# NeoPixel-WS2812B-2020.net
KiCad netlist of a schematic drawn in EAGLE
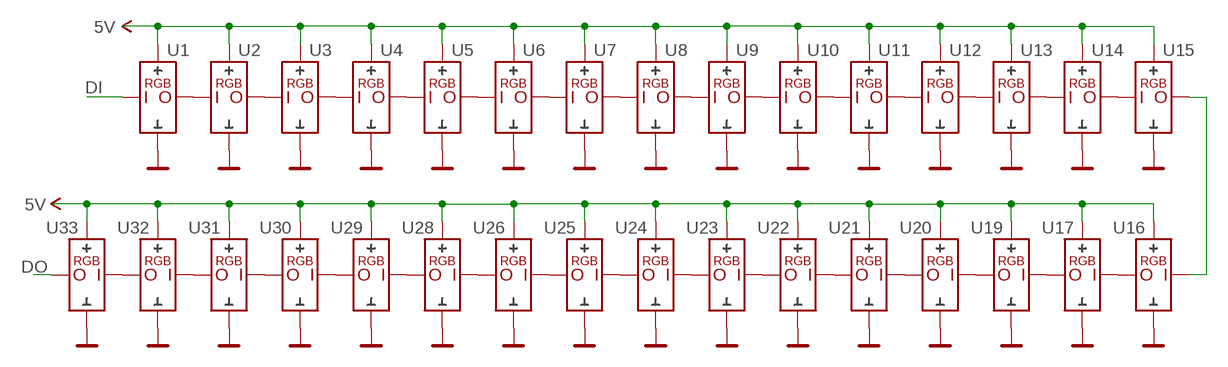
[diagram p0: schematic, sheet 1]

(export (version "E")
  (design (tool "Eeschema 10.0.6"))
  (components
    (comp (ref "U1")
      (value "LED-ADDRESSABLE16MM")
      (footprint "eagle-import:LED-WS2812B-2020-RING")
      (libsource (lib "eagle-import") (part "LED-ADDRESSABLE16MM"))
    )
    (comp (ref "U2")
      (value "LED-ADDRESSABLE16MM")
      (footprint "eagle-import:LED-WS2812B-2020-RING")
      (libsource (lib "eagle-import") (part "LED-ADDRESSABLE16MM"))
    )
    (comp (ref "U3")
      (value "LED-ADDRESSABLE16MM")
      (footprint "eagle-import:LED-WS2812B-2020-RING")
      (libsource (lib "eagle-import") (part "LED-ADDRESSABLE16MM"))
    )
    (comp (ref "U4")
      (value "LED-ADDRESSABLE16MM")
      (footprint "eagle-import:LED-WS2812B-2020-RING")
      (libsource (lib "eagle-import") (part "LED-ADDRESSABLE16MM"))
    )
    (comp (ref "U5")
      (value "LED-ADDRESSABLE16MM")
      (footprint "eagle-import:LED-WS2812B-2020-RING")
      (libsource (lib "eagle-import") (part "LED-ADDRESSABLE16MM"))
    )
    (comp (ref "U6")
      (value "LED-ADDRESSABLE16MM")
      (footprint "eagle-import:LED-WS2812B-2020-RING")
      (libsource (lib "eagle-import") (part "LED-ADDRESSABLE16MM"))
    )
    (comp (ref "U7")
      (value "LED-ADDRESSABLE16MM")
      (footprint "eagle-import:LED-WS2812B-2020-RING")
      (libsource (lib "eagle-import") (part "LED-ADDRESSABLE16MM"))
    )
    (comp (ref "U8")
      (value "LED-ADDRESSABLE16MM")
      (footprint "eagle-import:LED-WS2812B-2020-RING")
      (libsource (lib "eagle-import") (part "LED-ADDRESSABLE16MM"))
    )
    (comp (ref "U9")
      (value "LED-ADDRESSABLE16MM")
      (footprint "eagle-import:LED-WS2812B-2020-RING")
      (libsource (lib "eagle-import") (part "LED-ADDRESSABLE16MM"))
    )
    (comp (ref "U10")
      (value "LED-ADDRESSABLE16MM")
      (footprint "eagle-import:LED-WS2812B-2020-RING")
      (libsource (lib "eagle-import") (part "LED-ADDRESSABLE16MM"))
    )
    (comp (ref "U11")
      (value "LED-ADDRESSABLE16MM")
      (footprint "eagle-import:LED-WS2812B-2020-RING")
      (libsource (lib "eagle-import") (part "LED-ADDRESSABLE16MM"))
    )
    (comp (ref "U12")
      (value "LED-ADDRESSABLE16MM")
      (footprint "eagle-import:LED-WS2812B-2020-RING")
      (libsource (lib "eagle-import") (part "LED-ADDRESSABLE16MM"))
    )
    (comp (ref "U13")
      (value "LED-ADDRESSABLE16MM")
      (footprint "eagle-import:LED-WS2812B-2020-RING")
      (libsource (lib "eagle-import") (part "LED-ADDRESSABLE16MM"))
    )
    (comp (ref "U14")
      (value "LED-ADDRESSABLE16MM")
      (footprint "eagle-import:LED-WS2812B-2020-RING")
      (libsource (lib "eagle-import") (part "LED-ADDRESSABLE16MM"))
    )
    (comp (ref "U15")
      (value "LED-ADDRESSABLE16MM")
      (footprint "eagle-import:LED-WS2812B-2020-RING")
      (libsource (lib "eagle-import") (part "LED-ADDRESSABLE16MM"))
    )
    (comp (ref "U16")
      (value "LED-ADDRESSABLE16MM")
      (footprint "eagle-import:LED-WS2812B-2020-RING")
      (libsource (lib "eagle-import") (part "LED-ADDRESSABLE16MM"))
    )
    (comp (ref "U17")
      (value "LED-ADDRESSABLE16MM")
      (footprint "eagle-import:LED-WS2812B-2020-RING")
      (libsource (lib "eagle-import") (part "LED-ADDRESSABLE16MM"))
    )
    (comp (ref "U19")
      (value "LED-ADDRESSABLE16MM")
      (footprint "eagle-import:LED-WS2812B-2020-RING")
      (libsource (lib "eagle-import") (part "LED-ADDRESSABLE16MM"))
    )
    (comp (ref "U20")
      (value "LED-ADDRESSABLE16MM")
      (footprint "eagle-import:LED-WS2812B-2020-RING")
      (libsource (lib "eagle-import") (part "LED-ADDRESSABLE16MM"))
    )
    (comp (ref "U21")
      (value "LED-ADDRESSABLE16MM")
      (footprint "eagle-import:LED-WS2812B-2020-RING")
      (libsource (lib "eagle-import") (part "LED-ADDRESSABLE16MM"))
    )
    (comp (ref "U22")
      (value "LED-ADDRESSABLE16MM")
      (footprint "eagle-import:LED-WS2812B-2020-RING")
      (libsource (lib "eagle-import") (part "LED-ADDRESSABLE16MM"))
    )
    (comp (ref "U23")
      (value "LED-ADDRESSABLE16MM")
      (footprint "eagle-import:LED-WS2812B-2020-RING")
      (libsource (lib "eagle-import") (part "LED-ADDRESSABLE16MM"))
    )
    (comp (ref "U24")
      (value "LED-ADDRESSABLE16MM")
      (footprint "eagle-import:LED-WS2812B-2020-RING")
      (libsource (lib "eagle-import") (part "LED-ADDRESSABLE16MM"))
    )
    (comp (ref "U25")
      (value "LED-ADDRESSABLE16MM")
      (footprint "eagle-import:LED-WS2812B-2020-RING")
      (libsource (lib "eagle-import") (part "LED-ADDRESSABLE16MM"))
    )
    (comp (ref "U26")
      (value "LED-ADDRESSABLE16MM")
      (footprint "eagle-import:LED-WS2812B-2020-RING")
      (libsource (lib "eagle-import") (part "LED-ADDRESSABLE16MM"))
    )
    (comp (ref "U28")
      (value "LED-ADDRESSABLE16MM")
      (footprint "eagle-import:LED-WS2812B-2020-RING")
      (libsource (lib "eagle-import") (part "LED-ADDRESSABLE16MM"))
    )
    (comp (ref "U29")
      (value "LED-ADDRESSABLE16MM")
      (footprint "eagle-import:LED-WS2812B-2020-RING")
      (libsource (lib "eagle-import") (part "LED-ADDRESSABLE16MM"))
    )
    (comp (ref "U30")
      (value "LED-ADDRESSABLE16MM")
      (footprint "eagle-import:LED-WS2812B-2020-RING")
      (libsource (lib "eagle-import") (part "LED-ADDRESSABLE16MM"))
    )
    (comp (ref "U31")
      (value "LED-ADDRESSABLE16MM")
      (footprint "eagle-import:LED-WS2812B-2020-RING")
      (libsource (lib "eagle-import") (part "LED-ADDRESSABLE16MM"))
    )
    (comp (ref "U32")
      (value "LED-ADDRESSABLE16MM")
      (footprint "eagle-import:LED-WS2812B-2020-RING")
      (libsource (lib "eagle-import") (part "LED-ADDRESSABLE16MM"))
    )
    (comp (ref "U33")
      (value "LED-ADDRESSABLE16MM")
      (footprint "eagle-import:LED-WS2812B-2020-RING")
      (libsource (lib "eagle-import") (part "LED-ADDRESSABLE16MM"))
    )
  )
  (nets
    (net (code "1") (name "/5V") (class "Default")
      (node (ref "U1") (pin "+") (pinfunction "VDD_+") (pintype "bidirectional"))
      (node (ref "U10") (pin "+") (pinfunction "VDD_+") (pintype "bidirectional"))
      (node (ref "U11") (pin "+") (pinfunction "VDD_+") (pintype "bidirectional"))
      (node (ref "U12") (pin "+") (pinfunction "VDD_+") (pintype "bidirectional"))
      (node (ref "U13") (pin "+") (pinfunction "VDD_+") (pintype "bidirectional"))
      (node (ref "U14") (pin "+") (pinfunction "VDD_+") (pintype "bidirectional"))
      (node (ref "U15") (pin "+") (pinfunction "VDD_+") (pintype "bidirectional"))
      (node (ref "U16") (pin "+") (pinfunction "VDD_+") (pintype "bidirectional"))
      (node (ref "U17") (pin "+") (pinfunction "VDD_+") (pintype "bidirectional"))
      (node (ref "U19") (pin "+") (pinfunction "VDD_+") (pintype "bidirectional"))
      (node (ref "U2") (pin "+") (pinfunction "VDD_+") (pintype "bidirectional"))
      (node (ref "U20") (pin "+") (pinfunction "VDD_+") (pintype "bidirectional"))
      (node (ref "U21") (pin "+") (pinfunction "VDD_+") (pintype "bidirectional"))
      (node (ref "U22") (pin "+") (pinfunction "VDD_+") (pintype "bidirectional"))
      (node (ref "U23") (pin "+") (pinfunction "VDD_+") (pintype "bidirectional"))
      (node (ref "U24") (pin "+") (pinfunction "VDD_+") (pintype "bidirectional"))
      (node (ref "U25") (pin "+") (pinfunction "VDD_+") (pintype "bidirectional"))
      (node (ref "U26") (pin "+") (pinfunction "VDD_+") (pintype "bidirectional"))
      (node (ref "U28") (pin "+") (pinfunction "VDD_+") (pintype "bidirectional"))
      (node (ref "U29") (pin "+") (pinfunction "VDD_+") (pintype "bidirectional"))
      (node (ref "U3") (pin "+") (pinfunction "VDD_+") (pintype "bidirectional"))
      (node (ref "U30") (pin "+") (pinfunction "VDD_+") (pintype "bidirectional"))
      (node (ref "U31") (pin "+") (pinfunction "VDD_+") (pintype "bidirectional"))
      (node (ref "U32") (pin "+") (pinfunction "VDD_+") (pintype "bidirectional"))
      (node (ref "U33") (pin "+") (pinfunction "VDD_+") (pintype "bidirectional"))
      (node (ref "U4") (pin "+") (pinfunction "VDD_+") (pintype "bidirectional"))
      (node (ref "U5") (pin "+") (pinfunction "VDD_+") (pintype "bidirectional"))
      (node (ref "U6") (pin "+") (pinfunction "VDD_+") (pintype "bidirectional"))
      (node (ref "U7") (pin "+") (pinfunction "VDD_+") (pintype "bidirectional"))
      (node (ref "U8") (pin "+") (pinfunction "VDD_+") (pintype "bidirectional"))
      (node (ref "U9") (pin "+") (pinfunction "VDD_+") (pintype "bidirectional"))
    )
    (net (code "2") (name "/DI") (class "Default")
      (node (ref "U1") (pin "DI") (pinfunction "DI_DI") (pintype "bidirectional"))
    )
    (net (code "3") (name "/DO") (class "Default")
      (node (ref "U33") (pin "DO") (pinfunction "DO_DO") (pintype "bidirectional"))
    )
    (net (code "4") (name "GND") (class "Default")
      (node (ref "U1") (pin "GND") (pinfunction "GND_GND") (pintype "bidirectional"))
      (node (ref "U10") (pin "GND") (pinfunction "GND_GND") (pintype "bidirectional"))
      (node (ref "U11") (pin "GND") (pinfunction "GND_GND") (pintype "bidirectional"))
      (node (ref "U12") (pin "GND") (pinfunction "GND_GND") (pintype "bidirectional"))
      (node (ref "U13") (pin "GND") (pinfunction "GND_GND") (pintype "bidirectional"))
      (node (ref "U14") (pin "GND") (pinfunction "GND_GND") (pintype "bidirectional"))
      (node (ref "U15") (pin "GND") (pinfunction "GND_GND") (pintype "bidirectional"))
      (node (ref "U16") (pin "GND") (pinfunction "GND_GND") (pintype "bidirectional"))
      (node (ref "U17") (pin "GND") (pinfunction "GND_GND") (pintype "bidirectional"))
      (node (ref "U19") (pin "GND") (pinfunction "GND_GND") (pintype "bidirectional"))
      (node (ref "U2") (pin "GND") (pinfunction "GND_GND") (pintype "bidirectional"))
      (node (ref "U20") (pin "GND") (pinfunction "GND_GND") (pintype "bidirectional"))
      (node (ref "U21") (pin "GND") (pinfunction "GND_GND") (pintype "bidirectional"))
      (node (ref "U22") (pin "GND") (pinfunction "GND_GND") (pintype "bidirectional"))
      (node (ref "U23") (pin "GND") (pinfunction "GND_GND") (pintype "bidirectional"))
      (node (ref "U24") (pin "GND") (pinfunction "GND_GND") (pintype "bidirectional"))
      (node (ref "U25") (pin "GND") (pinfunction "GND_GND") (pintype "bidirectional"))
      (node (ref "U26") (pin "GND") (pinfunction "GND_GND") (pintype "bidirectional"))
      (node (ref "U28") (pin "GND") (pinfunction "GND_GND") (pintype "bidirectional"))
      (node (ref "U29") (pin "GND") (pinfunction "GND_GND") (pintype "bidirectional"))
      (node (ref "U3") (pin "GND") (pinfunction "GND_GND") (pintype "bidirectional"))
      (node (ref "U30") (pin "GND") (pinfunction "GND_GND") (pintype "bidirectional"))
      (node (ref "U31") (pin "GND") (pinfunction "GND_GND") (pintype "bidirectional"))
      (node (ref "U32") (pin "GND") (pinfunction "GND_GND") (pintype "bidirectional"))
      (node (ref "U33") (pin "GND") (pinfunction "GND_GND") (pintype "bidirectional"))
      (node (ref "U4") (pin "GND") (pinfunction "GND_GND") (pintype "bidirectional"))
      (node (ref "U5") (pin "GND") (pinfunction "GND_GND") (pintype "bidirectional"))
      (node (ref "U6") (pin "GND") (pinfunction "GND_GND") (pintype "bidirectional"))
      (node (ref "U7") (pin "GND") (pinfunction "GND_GND") (pintype "bidirectional"))
      (node (ref "U8") (pin "GND") (pinfunction "GND_GND") (pintype "bidirectional"))
      (node (ref "U9") (pin "GND") (pinfunction "GND_GND") (pintype "bidirectional"))
    )
    (net (code "5") (name "Net-(U1-PadDO)") (class "Default")
      (node (ref "U1") (pin "DO") (pinfunction "DO_DO") (pintype "bidirectional"))
      (node (ref "U2") (pin "DI") (pinfunction "DI_DI") (pintype "bidirectional"))
    )
    (net (code "6") (name "Net-(U2-PadDO)") (class "Default")
      (node (ref "U2") (pin "DO") (pinfunction "DO_DO") (pintype "bidirectional"))
      (node (ref "U3") (pin "DI") (pinfunction "DI_DI") (pintype "bidirectional"))
    )
    (net (code "7") (name "Net-(U3-PadDO)") (class "Default")
      (node (ref "U3") (pin "DO") (pinfunction "DO_DO") (pintype "bidirectional"))
      (node (ref "U4") (pin "DI") (pinfunction "DI_DI") (pintype "bidirectional"))
    )
    (net (code "8") (name "Net-(U4-PadDO)") (class "Default")
      (node (ref "U4") (pin "DO") (pinfunction "DO_DO") (pintype "bidirectional"))
      (node (ref "U5") (pin "DI") (pinfunction "DI_DI") (pintype "bidirectional"))
    )
    (net (code "9") (name "Net-(U5-PadDO)") (class "Default")
      (node (ref "U5") (pin "DO") (pinfunction "DO_DO") (pintype "bidirectional"))
      (node (ref "U6") (pin "DI") (pinfunction "DI_DI") (pintype "bidirectional"))
    )
    (net (code "10") (name "Net-(U6-PadDO)") (class "Default")
      (node (ref "U6") (pin "DO") (pinfunction "DO_DO") (pintype "bidirectional"))
      (node (ref "U7") (pin "DI") (pinfunction "DI_DI") (pintype "bidirectional"))
    )
    (net (code "11") (name "Net-(U7-PadDO)") (class "Default")
      (node (ref "U7") (pin "DO") (pinfunction "DO_DO") (pintype "bidirectional"))
      (node (ref "U8") (pin "DI") (pinfunction "DI_DI") (pintype "bidirectional"))
    )
    (net (code "12") (name "Net-(U8-PadDO)") (class "Default")
      (node (ref "U8") (pin "DO") (pinfunction "DO_DO") (pintype "bidirectional"))
      (node (ref "U9") (pin "DI") (pinfunction "DI_DI") (pintype "bidirectional"))
    )
    (net (code "13") (name "Net-(U10-PadDI)") (class "Default")
      (node (ref "U10") (pin "DI") (pinfunction "DI_DI") (pintype "bidirectional"))
      (node (ref "U9") (pin "DO") (pinfunction "DO_DO") (pintype "bidirectional"))
    )
    (net (code "14") (name "Net-(U10-PadDO)") (class "Default")
      (node (ref "U10") (pin "DO") (pinfunction "DO_DO") (pintype "bidirectional"))
      (node (ref "U11") (pin "DI") (pinfunction "DI_DI") (pintype "bidirectional"))
    )
    (net (code "15") (name "Net-(U11-PadDO)") (class "Default")
      (node (ref "U11") (pin "DO") (pinfunction "DO_DO") (pintype "bidirectional"))
      (node (ref "U12") (pin "DI") (pinfunction "DI_DI") (pintype "bidirectional"))
    )
    (net (code "16") (name "Net-(U12-PadDO)") (class "Default")
      (node (ref "U12") (pin "DO") (pinfunction "DO_DO") (pintype "bidirectional"))
      (node (ref "U13") (pin "DI") (pinfunction "DI_DI") (pintype "bidirectional"))
    )
    (net (code "17") (name "Net-(U13-PadDO)") (class "Default")
      (node (ref "U13") (pin "DO") (pinfunction "DO_DO") (pintype "bidirectional"))
      (node (ref "U14") (pin "DI") (pinfunction "DI_DI") (pintype "bidirectional"))
    )
    (net (code "18") (name "Net-(U14-PadDO)") (class "Default")
      (node (ref "U14") (pin "DO") (pinfunction "DO_DO") (pintype "bidirectional"))
      (node (ref "U15") (pin "DI") (pinfunction "DI_DI") (pintype "bidirectional"))
    )
    (net (code "19") (name "Net-(U15-PadDO)") (class "Default")
      (node (ref "U15") (pin "DO") (pinfunction "DO_DO") (pintype "bidirectional"))
      (node (ref "U16") (pin "DI") (pinfunction "DI_DI") (pintype "bidirectional"))
    )
    (net (code "20") (name "Net-(U16-PadDO)") (class "Default")
      (node (ref "U16") (pin "DO") (pinfunction "DO_DO") (pintype "bidirectional"))
      (node (ref "U17") (pin "DI") (pinfunction "DI_DI") (pintype "bidirectional"))
    )
    (net (code "21") (name "Net-(U17-PadDO)") (class "Default")
      (node (ref "U17") (pin "DO") (pinfunction "DO_DO") (pintype "bidirectional"))
      (node (ref "U19") (pin "DI") (pinfunction "DI_DI") (pintype "bidirectional"))
    )
    (net (code "22") (name "Net-(U19-PadDO)") (class "Default")
      (node (ref "U19") (pin "DO") (pinfunction "DO_DO") (pintype "bidirectional"))
      (node (ref "U20") (pin "DI") (pinfunction "DI_DI") (pintype "bidirectional"))
    )
    (net (code "23") (name "Net-(U20-PadDO)") (class "Default")
      (node (ref "U20") (pin "DO") (pinfunction "DO_DO") (pintype "bidirectional"))
      (node (ref "U21") (pin "DI") (pinfunction "DI_DI") (pintype "bidirectional"))
    )
    (net (code "24") (name "Net-(U21-PadDO)") (class "Default")
      (node (ref "U21") (pin "DO") (pinfunction "DO_DO") (pintype "bidirectional"))
      (node (ref "U22") (pin "DI") (pinfunction "DI_DI") (pintype "bidirectional"))
    )
    (net (code "25") (name "Net-(U22-PadDO)") (class "Default")
      (node (ref "U22") (pin "DO") (pinfunction "DO_DO") (pintype "bidirectional"))
      (node (ref "U23") (pin "DI") (pinfunction "DI_DI") (pintype "bidirectional"))
    )
    (net (code "26") (name "Net-(U23-PadDO)") (class "Default")
      (node (ref "U23") (pin "DO") (pinfunction "DO_DO") (pintype "bidirectional"))
      (node (ref "U24") (pin "DI") (pinfunction "DI_DI") (pintype "bidirectional"))
    )
    (net (code "27") (name "Net-(U24-PadDO)") (class "Default")
      (node (ref "U24") (pin "DO") (pinfunction "DO_DO") (pintype "bidirectional"))
      (node (ref "U25") (pin "DI") (pinfunction "DI_DI") (pintype "bidirectional"))
    )
    (net (code "28") (name "Net-(U25-PadDO)") (class "Default")
      (node (ref "U25") (pin "DO") (pinfunction "DO_DO") (pintype "bidirectional"))
      (node (ref "U26") (pin "DI") (pinfunction "DI_DI") (pintype "bidirectional"))
    )
    (net (code "29") (name "Net-(U26-PadDO)") (class "Default")
      (node (ref "U26") (pin "DO") (pinfunction "DO_DO") (pintype "bidirectional"))
      (node (ref "U28") (pin "DI") (pinfunction "DI_DI") (pintype "bidirectional"))
    )
    (net (code "30") (name "Net-(U28-PadDO)") (class "Default")
      (node (ref "U28") (pin "DO") (pinfunction "DO_DO") (pintype "bidirectional"))
      (node (ref "U29") (pin "DI") (pinfunction "DI_DI") (pintype "bidirectional"))
    )
    (net (code "31") (name "Net-(U29-PadDO)") (class "Default")
      (node (ref "U29") (pin "DO") (pinfunction "DO_DO") (pintype "bidirectional"))
      (node (ref "U30") (pin "DI") (pinfunction "DI_DI") (pintype "bidirectional"))
    )
    (net (code "32") (name "Net-(U30-PadDO)") (class "Default")
      (node (ref "U30") (pin "DO") (pinfunction "DO_DO") (pintype "bidirectional"))
      (node (ref "U31") (pin "DI") (pinfunction "DI_DI") (pintype "bidirectional"))
    )
    (net (code "33") (name "Net-(U31-PadDO)") (class "Default")
      (node (ref "U31") (pin "DO") (pinfunction "DO_DO") (pintype "bidirectional"))
      (node (ref "U32") (pin "DI") (pinfunction "DI_DI") (pintype "bidirectional"))
    )
    (net (code "34") (name "Net-(U32-PadDO)") (class "Default")
      (node (ref "U32") (pin "DO") (pinfunction "DO_DO") (pintype "bidirectional"))
      (node (ref "U33") (pin "DI") (pinfunction "DI_DI") (pintype "bidirectional"))
    )
  )
)
